# SparkFun_IMU_Breakout_ICM-20948.net
KiCad netlist of a schematic drawn in EAGLE
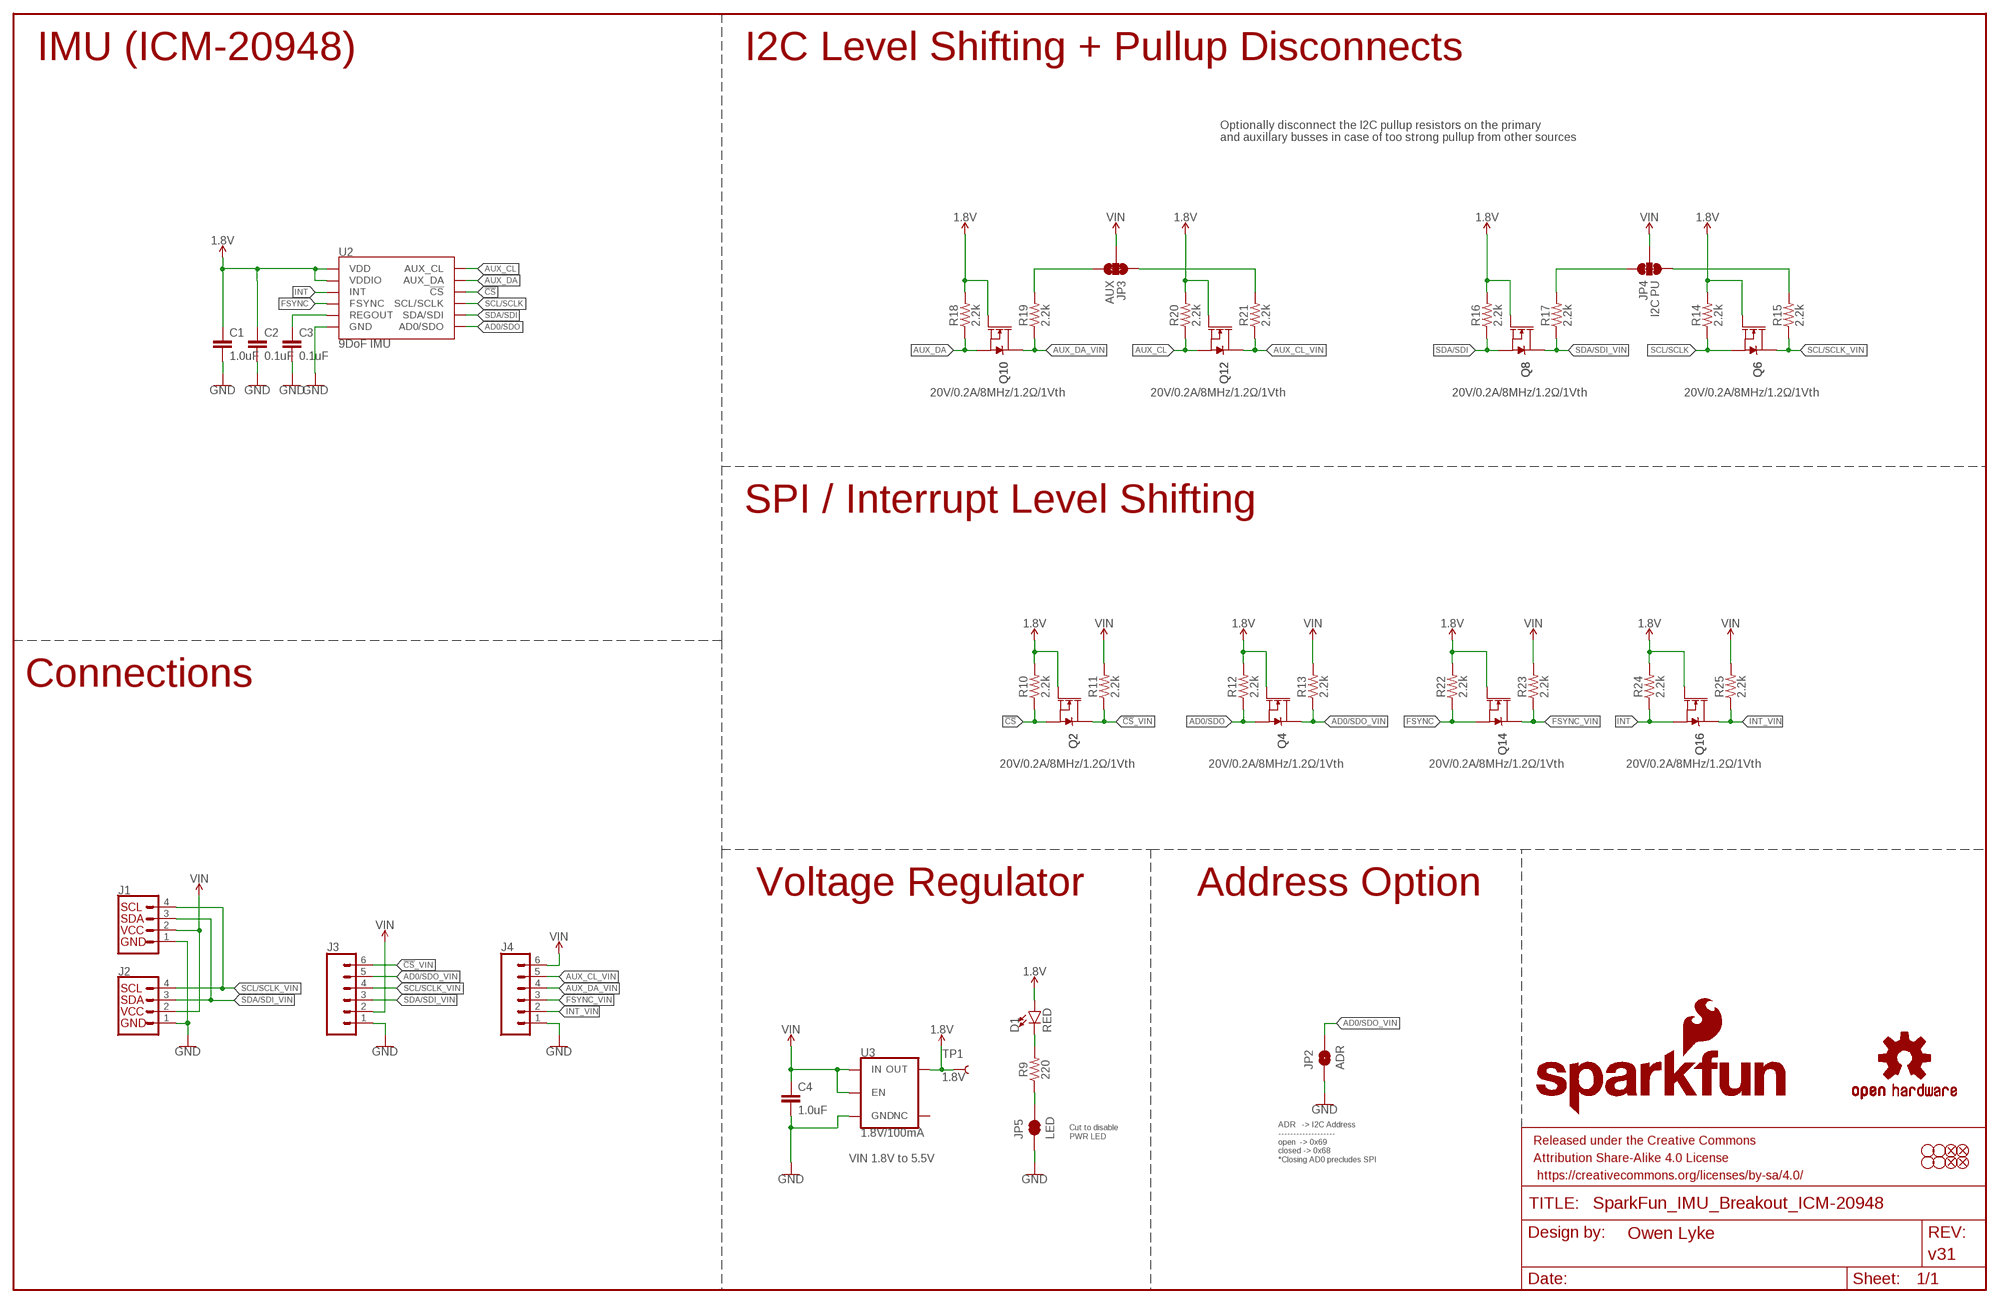
[diagram p0: schematic, sheet 1]

(export (version "E")
  (design (tool "Eeschema 10.0.6"))
  (components
    (comp (ref "C1")
      (value "1.0uF")
      (footprint "eagle-import:0603")
      (libsource (lib "eagle-import") (part "1.0UF-0603-16V-10%-X7R"))
    )
    (comp (ref "C2")
      (value "0.1uF")
      (footprint "eagle-import:0603")
      (libsource (lib "eagle-import") (part "0.1UF-0603-25V-5%"))
    )
    (comp (ref "C3")
      (value "0.1uF")
      (footprint "eagle-import:0603")
      (libsource (lib "eagle-import") (part "0.1UF-0603-25V-5%"))
    )
    (comp (ref "C4")
      (value "1.0uF")
      (footprint "eagle-import:0603")
      (libsource (lib "eagle-import") (part "1.0UF-0603-16V-10%-X7R"))
    )
    (comp (ref "D1")
      (value "RED")
      (footprint "eagle-import:LED-0603")
      (libsource (lib "eagle-import") (part "LED-RED0603"))
    )
    (comp (ref "FD1")
      (value "FIDUCIAL1X2")
      (footprint "eagle-import:FIDUCIAL-1X2")
      (libsource (lib "eagle-import") (part "FIDUCIAL1X2"))
    )
    (comp (ref "FD2")
      (value "FIDUCIAL1X2")
      (footprint "eagle-import:FIDUCIAL-1X2")
      (libsource (lib "eagle-import") (part "FIDUCIAL1X2"))
    )
    (comp (ref "FD3")
      (value "FIDUCIAL1X2")
      (footprint "eagle-import:FIDUCIAL-1X2")
      (libsource (lib "eagle-import") (part "FIDUCIAL1X2"))
    )
    (comp (ref "FD4")
      (value "FIDUCIAL1X2")
      (footprint "eagle-import:FIDUCIAL-1X2")
      (libsource (lib "eagle-import") (part "FIDUCIAL1X2"))
    )
    (comp (ref "FRAME2")
      (value "FRAME-LEDGER")
      (footprint "eagle-import:CREATIVE_COMMONS")
      (fields (field (name "DESIGNER") "Owen Lyke") (field (name "REV") "v31"))
      (libsource (lib "eagle-import") (part "FRAME-LEDGER"))
    )
    (comp (ref "H1")
      (value "STAND-OFF")
      (footprint "eagle-import:STAND-OFF")
      (libsource (lib "eagle-import") (part "STAND-OFF"))
    )
    (comp (ref "H2")
      (value "STAND-OFF")
      (footprint "eagle-import:STAND-OFF")
      (libsource (lib "eagle-import") (part "STAND-OFF"))
    )
    (comp (ref "H3")
      (value "STAND-OFF")
      (footprint "eagle-import:STAND-OFF")
      (libsource (lib "eagle-import") (part "STAND-OFF"))
    )
    (comp (ref "H4")
      (value "STAND-OFF")
      (footprint "eagle-import:STAND-OFF")
      (libsource (lib "eagle-import") (part "STAND-OFF"))
    )
    (comp (ref "J1")
      (value "QWIIC_CONNECTORJS-1MM")
      (footprint "eagle-import:JST04_1MM_RA")
      (libsource (lib "eagle-import") (part "QWIIC_CONNECTORJS-1MM"))
    )
    (comp (ref "J2")
      (value "QWIIC_CONNECTORJS-1MM")
      (footprint "eagle-import:JST04_1MM_RA")
      (libsource (lib "eagle-import") (part "QWIIC_CONNECTORJS-1MM"))
    )
    (comp (ref "J3")
      (value "CONN_06NO_SILK_NO_POP")
      (footprint "eagle-import:1X06_NO_SILK")
      (libsource (lib "eagle-import") (part "CONN_06NO_SILK_NO_POP"))
    )
    (comp (ref "J4")
      (value "CONN_06NO_SILK_NO_POP")
      (footprint "eagle-import:1X06_NO_SILK")
      (libsource (lib "eagle-import") (part "CONN_06NO_SILK_NO_POP"))
    )
    (comp (ref "JP2")
      (value "ADR")
      (footprint "eagle-import:SMT-JUMPER_2_NO_SILK")
      (libsource (lib "eagle-import") (part "JUMPER-SMT_2_NO_SILK"))
    )
    (comp (ref "JP3")
      (value "AUX")
      (footprint "eagle-import:SMT-JUMPER_3_2-NC_TRACE_SILK")
      (libsource (lib "eagle-import") (part "JUMPER-SMT_3_2-NC_TRACE_SILK"))
    )
    (comp (ref "JP4")
      (value "I2C PU")
      (footprint "eagle-import:SMT-JUMPER_3_2-NC_TRACE_SILK")
      (libsource (lib "eagle-import") (part "JUMPER-SMT_3_2-NC_TRACE_SILK"))
    )
    (comp (ref "JP5")
      (value "LED")
      (footprint "eagle-import:SMT-JUMPER_2_NC_TRACE_SILK")
      (libsource (lib "eagle-import") (part "JUMPER-SMT_2_NC_TRACE_SILK"))
    )
    (comp (ref "LOGO1")
      (value "SFE_LOGO_NAME_FLAME.1_INCH")
      (footprint "eagle-import:SFE_LOGO_NAME_FLAME_.1")
      (libsource (lib "eagle-import") (part "SFE_LOGO_NAME_FLAME.1_INCH"))
    )
    (comp (ref "LOGO2")
      (value "OSHW-LOGOMINI")
      (footprint "eagle-import:OSHW-LOGO-MINI")
      (libsource (lib "eagle-import") (part "OSHW-LOGOMINI"))
    )
    (comp (ref "Q2")
      (value "20V/0.2A/8MHz/1.2Ω/1Vth")
      (footprint "eagle-import:SOT-416FL")
      (libsource (lib "eagle-import") (part "MOSFET-NCH-RE1C002UN"))
    )
    (comp (ref "Q4")
      (value "20V/0.2A/8MHz/1.2Ω/1Vth")
      (footprint "eagle-import:SOT-416FL")
      (libsource (lib "eagle-import") (part "MOSFET-NCH-RE1C002UN"))
    )
    (comp (ref "Q6")
      (value "20V/0.2A/8MHz/1.2Ω/1Vth")
      (footprint "eagle-import:SOT-416FL")
      (libsource (lib "eagle-import") (part "MOSFET-NCH-RE1C002UN"))
    )
    (comp (ref "Q8")
      (value "20V/0.2A/8MHz/1.2Ω/1Vth")
      (footprint "eagle-import:SOT-416FL")
      (libsource (lib "eagle-import") (part "MOSFET-NCH-RE1C002UN"))
    )
    (comp (ref "Q10")
      (value "20V/0.2A/8MHz/1.2Ω/1Vth")
      (footprint "eagle-import:SOT-416FL")
      (libsource (lib "eagle-import") (part "MOSFET-NCH-RE1C002UN"))
    )
    (comp (ref "Q12")
      (value "20V/0.2A/8MHz/1.2Ω/1Vth")
      (footprint "eagle-import:SOT-416FL")
      (libsource (lib "eagle-import") (part "MOSFET-NCH-RE1C002UN"))
    )
    (comp (ref "Q14")
      (value "20V/0.2A/8MHz/1.2Ω/1Vth")
      (footprint "eagle-import:SOT-416FL")
      (libsource (lib "eagle-import") (part "MOSFET-NCH-RE1C002UN"))
    )
    (comp (ref "Q16")
      (value "20V/0.2A/8MHz/1.2Ω/1Vth")
      (footprint "eagle-import:SOT-416FL")
      (libsource (lib "eagle-import") (part "MOSFET-NCH-RE1C002UN"))
    )
    (comp (ref "R9")
      (value "220")
      (footprint "eagle-import:0603")
      (libsource (lib "eagle-import") (part "220OHM-0603-1/10W-1%"))
    )
    (comp (ref "R10")
      (value "2.2k")
      (footprint "eagle-import:0402-TIGHT")
      (libsource (lib "eagle-import") (part "2.2KOHM-0402T-1/16W-1%"))
    )
    (comp (ref "R11")
      (value "2.2k")
      (footprint "eagle-import:0402-TIGHT")
      (libsource (lib "eagle-import") (part "2.2KOHM-0402T-1/16W-1%"))
    )
    (comp (ref "R12")
      (value "2.2k")
      (footprint "eagle-import:0402-TIGHT")
      (libsource (lib "eagle-import") (part "2.2KOHM-0402T-1/16W-1%"))
    )
    (comp (ref "R13")
      (value "2.2k")
      (footprint "eagle-import:0402-TIGHT")
      (libsource (lib "eagle-import") (part "2.2KOHM-0402T-1/16W-1%"))
    )
    (comp (ref "R14")
      (value "2.2k")
      (footprint "eagle-import:0402-TIGHT")
      (libsource (lib "eagle-import") (part "2.2KOHM-0402T-1/16W-1%"))
    )
    (comp (ref "R15")
      (value "2.2k")
      (footprint "eagle-import:0402-TIGHT")
      (libsource (lib "eagle-import") (part "2.2KOHM-0402T-1/16W-1%"))
    )
    (comp (ref "R16")
      (value "2.2k")
      (footprint "eagle-import:0402-TIGHT")
      (libsource (lib "eagle-import") (part "2.2KOHM-0402T-1/16W-1%"))
    )
    (comp (ref "R17")
      (value "2.2k")
      (footprint "eagle-import:0402-TIGHT")
      (libsource (lib "eagle-import") (part "2.2KOHM-0402T-1/16W-1%"))
    )
    (comp (ref "R18")
      (value "2.2k")
      (footprint "eagle-import:0402-TIGHT")
      (libsource (lib "eagle-import") (part "2.2KOHM-0402T-1/16W-1%"))
    )
    (comp (ref "R19")
      (value "2.2k")
      (footprint "eagle-import:0402-TIGHT")
      (libsource (lib "eagle-import") (part "2.2KOHM-0402T-1/16W-1%"))
    )
    (comp (ref "R20")
      (value "2.2k")
      (footprint "eagle-import:0402-TIGHT")
      (libsource (lib "eagle-import") (part "2.2KOHM-0402T-1/16W-1%"))
    )
    (comp (ref "R21")
      (value "2.2k")
      (footprint "eagle-import:0402-TIGHT")
      (libsource (lib "eagle-import") (part "2.2KOHM-0402T-1/16W-1%"))
    )
    (comp (ref "R22")
      (value "2.2k")
      (footprint "eagle-import:0402-TIGHT")
      (libsource (lib "eagle-import") (part "2.2KOHM-0402T-1/16W-1%"))
    )
    (comp (ref "R23")
      (value "2.2k")
      (footprint "eagle-import:0402-TIGHT")
      (libsource (lib "eagle-import") (part "2.2KOHM-0402T-1/16W-1%"))
    )
    (comp (ref "R24")
      (value "2.2k")
      (footprint "eagle-import:0402-TIGHT")
      (libsource (lib "eagle-import") (part "2.2KOHM-0402T-1/16W-1%"))
    )
    (comp (ref "R25")
      (value "2.2k")
      (footprint "eagle-import:0402-TIGHT")
      (libsource (lib "eagle-import") (part "2.2KOHM-0402T-1/16W-1%"))
    )
    (comp (ref "TP1")
      (value "1.8V")
      (footprint "eagle-import:PAD.03X.03")
      (libsource (lib "eagle-import") (part "TEST-POINT3"))
    )
    (comp (ref "U2")
      (value "9DoF IMU")
      (footprint "eagle-import:QFN24-3X3")
      (libsource (lib "eagle-import") (part "ICM-20948"))
    )
    (comp (ref "U3")
      (value "1.8V/100mA")
      (footprint "eagle-import:SC70")
      (libsource (lib "eagle-import") (part "V_REG_SP6214-1.8V"))
    )
  )
  (nets
    (net (code "1") (name "/~{CS}") (class "Default")
      (node (ref "Q2") (pin "2") (pinfunction "S_2") (pintype "bidirectional"))
      (node (ref "R10") (pin "1") (pinfunction "1_1") (pintype "passive"))
      (node (ref "U2") (pin "22") (pinfunction "~{CS}_22") (pintype "bidirectional"))
    )
    (net (code "2") (name "/~{CS}_VIN") (class "Default")
      (node (ref "J3") (pin "6") (pinfunction "6_6") (pintype "passive"))
      (node (ref "Q2") (pin "3") (pinfunction "D_3") (pintype "bidirectional"))
      (node (ref "R11") (pin "1") (pinfunction "1_1") (pintype "passive"))
    )
    (net (code "3") (name "1.8V") (class "Default")
      (node (ref "C1") (pin "1") (pinfunction "1_1") (pintype "passive"))
      (node (ref "C2") (pin "1") (pinfunction "1_1") (pintype "passive"))
      (node (ref "D1") (pin "A") (pinfunction "A_A") (pintype "passive"))
      (node (ref "Q10") (pin "1") (pinfunction "G_1") (pintype "bidirectional"))
      (node (ref "Q12") (pin "1") (pinfunction "G_1") (pintype "bidirectional"))
      (node (ref "Q14") (pin "1") (pinfunction "G_1") (pintype "bidirectional"))
      (node (ref "Q16") (pin "1") (pinfunction "G_1") (pintype "bidirectional"))
      (node (ref "Q2") (pin "1") (pinfunction "G_1") (pintype "bidirectional"))
      (node (ref "Q4") (pin "1") (pinfunction "G_1") (pintype "bidirectional"))
      (node (ref "Q6") (pin "1") (pinfunction "G_1") (pintype "bidirectional"))
      (node (ref "Q8") (pin "1") (pinfunction "G_1") (pintype "bidirectional"))
      (node (ref "R10") (pin "2") (pinfunction "2_2") (pintype "passive"))
      (node (ref "R12") (pin "2") (pinfunction "2_2") (pintype "passive"))
      (node (ref "R14") (pin "2") (pinfunction "2_2") (pintype "passive"))
      (node (ref "R16") (pin "2") (pinfunction "2_2") (pintype "passive"))
      (node (ref "R18") (pin "2") (pinfunction "2_2") (pintype "passive"))
      (node (ref "R20") (pin "2") (pinfunction "2_2") (pintype "passive"))
      (node (ref "R22") (pin "2") (pinfunction "2_2") (pintype "passive"))
      (node (ref "R24") (pin "2") (pinfunction "2_2") (pintype "passive"))
      (node (ref "TP1") (pin "P$1") (pinfunction "1_P$1") (pintype "bidirectional"))
      (node (ref "U2") (pin "13") (pinfunction "VDD_13") (pintype "bidirectional"))
      (node (ref "U2") (pin "8") (pinfunction "VDDIO_8") (pintype "bidirectional"))
      (node (ref "U3") (pin "5") (pinfunction "OUT_5") (pintype "passive"))
    )
    (net (code "4") (name "AD0{slash}SDO") (class "Default")
      (node (ref "Q4") (pin "2") (pinfunction "S_2") (pintype "bidirectional"))
      (node (ref "R12") (pin "1") (pinfunction "1_1") (pintype "passive"))
      (node (ref "U2") (pin "9") (pinfunction "AD0/SDO_9") (pintype "bidirectional"))
    )
    (net (code "5") (name "AD0{slash}SDO_VIN") (class "Default")
      (node (ref "J3") (pin "5") (pinfunction "5_5") (pintype "passive"))
      (node (ref "JP2") (pin "2") (pinfunction "2_2") (pintype "passive"))
      (node (ref "Q4") (pin "3") (pinfunction "D_3") (pintype "bidirectional"))
      (node (ref "R13") (pin "1") (pinfunction "1_1") (pintype "passive"))
    )
    (net (code "6") (name "AUX_CL") (class "Default")
      (node (ref "Q12") (pin "2") (pinfunction "S_2") (pintype "bidirectional"))
      (node (ref "R20") (pin "1") (pinfunction "1_1") (pintype "passive"))
      (node (ref "U2") (pin "7") (pinfunction "AUX_CL_7") (pintype "bidirectional"))
    )
    (net (code "7") (name "AUX_CL_VIN") (class "Default")
      (node (ref "J4") (pin "5") (pinfunction "5_5") (pintype "passive"))
      (node (ref "Q12") (pin "3") (pinfunction "D_3") (pintype "bidirectional"))
      (node (ref "R21") (pin "1") (pinfunction "1_1") (pintype "passive"))
    )
    (net (code "8") (name "AUX_DA") (class "Default")
      (node (ref "Q10") (pin "2") (pinfunction "S_2") (pintype "bidirectional"))
      (node (ref "R18") (pin "1") (pinfunction "1_1") (pintype "passive"))
      (node (ref "U2") (pin "21") (pinfunction "AUX_DA_21") (pintype "bidirectional"))
    )
    (net (code "9") (name "AUX_DA_VIN") (class "Default")
      (node (ref "J4") (pin "4") (pinfunction "4_4") (pintype "passive"))
      (node (ref "Q10") (pin "3") (pinfunction "D_3") (pintype "bidirectional"))
      (node (ref "R19") (pin "1") (pinfunction "1_1") (pintype "passive"))
    )
    (net (code "10") (name "FSYNC") (class "Default")
      (node (ref "Q14") (pin "2") (pinfunction "S_2") (pintype "bidirectional"))
      (node (ref "R22") (pin "1") (pinfunction "1_1") (pintype "passive"))
      (node (ref "U2") (pin "11") (pinfunction "FSYNC_11") (pintype "bidirectional"))
    )
    (net (code "11") (name "FSYNC_VIN") (class "Default")
      (node (ref "J4") (pin "3") (pinfunction "3_3") (pintype "passive"))
      (node (ref "Q14") (pin "3") (pinfunction "D_3") (pintype "bidirectional"))
      (node (ref "R23") (pin "1") (pinfunction "1_1") (pintype "passive"))
    )
    (net (code "12") (name "GND") (class "Default")
      (node (ref "C1") (pin "2") (pinfunction "2_2") (pintype "passive"))
      (node (ref "C2") (pin "2") (pinfunction "2_2") (pintype "passive"))
      (node (ref "C3") (pin "2") (pinfunction "2_2") (pintype "passive"))
      (node (ref "C4") (pin "2") (pinfunction "2_2") (pintype "passive"))
      (node (ref "J1") (pin "1") (pinfunction "1_1") (pintype "power_in"))
      (node (ref "J2") (pin "1") (pinfunction "1_1") (pintype "power_in"))
      (node (ref "J3") (pin "1") (pinfunction "1_1") (pintype "passive"))
      (node (ref "J4") (pin "1") (pinfunction "1_1") (pintype "passive"))
      (node (ref "JP2") (pin "1") (pinfunction "1_1") (pintype "passive"))
      (node (ref "JP5") (pin "1") (pinfunction "1_1") (pintype "passive"))
      (node (ref "U2") (pin "18") (pinfunction "GND_18") (pintype "bidirectional"))
      (node (ref "U2") (pin "20") (pinfunction "GND_20") (pintype "bidirectional"))
      (node (ref "U3") (pin "2") (pinfunction "GND_2") (pintype "input"))
    )
    (net (code "13") (name "INT") (class "Default")
      (node (ref "Q16") (pin "2") (pinfunction "S_2") (pintype "bidirectional"))
      (node (ref "R24") (pin "1") (pinfunction "1_1") (pintype "passive"))
      (node (ref "U2") (pin "12") (pinfunction "INT_12") (pintype "bidirectional"))
    )
    (net (code "14") (name "INT_VIN") (class "Default")
      (node (ref "J4") (pin "2") (pinfunction "2_2") (pintype "passive"))
      (node (ref "Q16") (pin "3") (pinfunction "D_3") (pintype "bidirectional"))
      (node (ref "R25") (pin "1") (pinfunction "1_1") (pintype "passive"))
    )
    (net (code "15") (name "Net-(D1-PadC)") (class "Default")
      (node (ref "D1") (pin "C") (pinfunction "C_C") (pintype "passive"))
      (node (ref "R9") (pin "2") (pinfunction "2_2") (pintype "passive"))
    )
    (net (code "16") (name "Net-(JP3-Pad1)") (class "Default")
      (node (ref "JP3") (pin "1") (pinfunction "1_1") (pintype "passive"))
      (node (ref "R21") (pin "2") (pinfunction "2_2") (pintype "passive"))
    )
    (net (code "17") (name "Net-(JP3-Pad3)") (class "Default")
      (node (ref "JP3") (pin "3") (pinfunction "3_3") (pintype "passive"))
      (node (ref "R19") (pin "2") (pinfunction "2_2") (pintype "passive"))
    )
    (net (code "18") (name "Net-(JP4-Pad1)") (class "Default")
      (node (ref "JP4") (pin "1") (pinfunction "1_1") (pintype "passive"))
      (node (ref "R17") (pin "2") (pinfunction "2_2") (pintype "passive"))
    )
    (net (code "19") (name "Net-(JP4-Pad3)") (class "Default")
      (node (ref "JP4") (pin "3") (pinfunction "3_3") (pintype "passive"))
      (node (ref "R15") (pin "2") (pinfunction "2_2") (pintype "passive"))
    )
    (net (code "20") (name "Net-(JP5-Pad2)") (class "Default")
      (node (ref "JP5") (pin "2") (pinfunction "2_2") (pintype "passive"))
      (node (ref "R9") (pin "1") (pinfunction "1_1") (pintype "passive"))
    )
    (net (code "21") (name "Net-(U2-REGOUT)") (class "Default")
      (node (ref "C3") (pin "1") (pinfunction "1_1") (pintype "passive"))
      (node (ref "U2") (pin "10") (pinfunction "REGOUT_10") (pintype "bidirectional"))
    )
    (net (code "22") (name "SCL{slash}SCLK") (class "Default")
      (node (ref "Q6") (pin "2") (pinfunction "S_2") (pintype "bidirectional"))
      (node (ref "R14") (pin "1") (pinfunction "1_1") (pintype "passive"))
      (node (ref "U2") (pin "23") (pinfunction "SCL/SCLK_23") (pintype "bidirectional"))
    )
    (net (code "23") (name "SCL{slash}SCLK_VIN") (class "Default")
      (node (ref "J1") (pin "4") (pinfunction "4_4") (pintype "passive"))
      (node (ref "J2") (pin "4") (pinfunction "4_4") (pintype "passive"))
      (node (ref "J3") (pin "4") (pinfunction "4_4") (pintype "passive"))
      (node (ref "Q6") (pin "3") (pinfunction "D_3") (pintype "bidirectional"))
      (node (ref "R15") (pin "1") (pinfunction "1_1") (pintype "passive"))
    )
    (net (code "24") (name "SDA{slash}SDI") (class "Default")
      (node (ref "Q8") (pin "2") (pinfunction "S_2") (pintype "bidirectional"))
      (node (ref "R16") (pin "1") (pinfunction "1_1") (pintype "passive"))
      (node (ref "U2") (pin "24") (pinfunction "SDA/SDI_24") (pintype "bidirectional"))
    )
    (net (code "25") (name "SDA{slash}SDI_VIN") (class "Default")
      (node (ref "J1") (pin "3") (pinfunction "3_3") (pintype "passive"))
      (node (ref "J2") (pin "3") (pinfunction "3_3") (pintype "passive"))
      (node (ref "J3") (pin "3") (pinfunction "3_3") (pintype "passive"))
      (node (ref "Q8") (pin "3") (pinfunction "D_3") (pintype "bidirectional"))
      (node (ref "R17") (pin "1") (pinfunction "1_1") (pintype "passive"))
    )
    (net (code "26") (name "VIN") (class "Default")
      (node (ref "C4") (pin "1") (pinfunction "1_1") (pintype "passive"))
      (node (ref "J1") (pin "2") (pinfunction "2_2") (pintype "power_in"))
      (node (ref "J2") (pin "2") (pinfunction "2_2") (pintype "power_in"))
      (node (ref "J3") (pin "2") (pinfunction "2_2") (pintype "passive"))
      (node (ref "J4") (pin "6") (pinfunction "6_6") (pintype "passive"))
      (node (ref "JP3") (pin "2") (pinfunction "2_2") (pintype "passive"))
      (node (ref "JP4") (pin "2") (pinfunction "2_2") (pintype "passive"))
      (node (ref "R11") (pin "2") (pinfunction "2_2") (pintype "passive"))
      (node (ref "R13") (pin "2") (pinfunction "2_2") (pintype "passive"))
      (node (ref "R23") (pin "2") (pinfunction "2_2") (pintype "passive"))
      (node (ref "R25") (pin "2") (pinfunction "2_2") (pintype "passive"))
      (node (ref "U3") (pin "1") (pinfunction "IN_1") (pintype "input"))
      (node (ref "U3") (pin "3") (pinfunction "EN_3") (pintype "input"))
    )
    (net (code "27") (name "unconnected-(U3-NC-Pad4)") (class "Default")
      (node (ref "U3") (pin "4") (pinfunction "NC_4") (pintype "no_connect"))
    )
  )
)
